# Remote_Board_V2_0.net
KiCad netlist of a schematic drawn in EAGLE
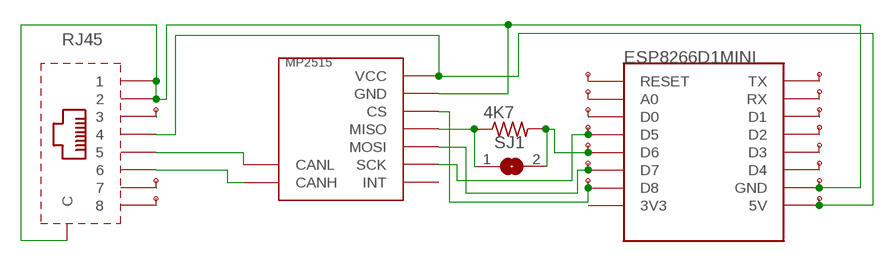
[diagram p0: schematic, sheet 1]

(export (version "E")
  (design (tool "Eeschema 10.0.6"))
  (components
    (comp (ref "4K7")
      (value "R-US_0207/10")
      (footprint "eagle-import:0207_10")
      (libsource (lib "eagle-import") (part "R-US_0207/10"))
    )
    (comp (ref "ESP8266D1MINI")
      (value "WEMOS-D1-MINI_SEM_LAYOUT")
      (footprint "eagle-import:WEMOS-D1-MINI_SEM_LAYOUT")
      (libsource (lib "eagle-import") (part "WEMOS-D1-MINI_SEM_LAYOUT"))
    )
    (comp (ref "RJ45")
      (value "ALI-RJ45_SEM_LAYOUT")
      (footprint "eagle-import:ALI-RJ45_SEM_LAYOUT")
      (libsource (lib "eagle-import") (part "ALI-RJ45_SEM_LAYOUT"))
    )
    (comp (ref "SJ1") (value "SJ") (footprint "eagle-import:SJ") (libsource (lib "eagle-import") (part "SJ")))
    (comp (ref "U$1") (value "TP") (footprint "eagle-import:TP") (libsource (lib "eagle-import") (part "TP")))
    (comp (ref "U$2") (value "TP") (footprint "eagle-import:TP") (libsource (lib "eagle-import") (part "TP")))
    (comp (ref "U$3") (value "TP") (footprint "eagle-import:TP") (libsource (lib "eagle-import") (part "TP")))
    (comp (ref "U$4") (value "TP") (footprint "eagle-import:TP") (libsource (lib "eagle-import") (part "TP")))
    (comp (ref "U$5") (value "TP") (footprint "eagle-import:TP") (libsource (lib "eagle-import") (part "TP")))
    (comp (ref "U$6") (value "TP") (footprint "eagle-import:TP") (libsource (lib "eagle-import") (part "TP")))
    (comp (ref "U$7") (value "TP") (footprint "eagle-import:TP") (libsource (lib "eagle-import") (part "TP")))
    (comp (ref "U$8") (value "TP") (footprint "eagle-import:TP") (libsource (lib "eagle-import") (part "TP")))
    (comp (ref "U$9") (value "TP") (footprint "eagle-import:TP") (libsource (lib "eagle-import") (part "TP")))
    (comp (ref "U$10")
      (value "TP")
      (footprint "eagle-import:TP")
      (libsource (lib "eagle-import") (part "TP"))
    )
    (comp (ref "U$11")
      (value "TP")
      (footprint "eagle-import:TP")
      (libsource (lib "eagle-import") (part "TP"))
    )
    (comp (ref "U$12")
      (value "TP")
      (footprint "eagle-import:TP")
      (libsource (lib "eagle-import") (part "TP"))
    )
    (comp (ref "U$13")
      (value "TP")
      (footprint "eagle-import:TP")
      (libsource (lib "eagle-import") (part "TP"))
    )
    (comp (ref "U$14")
      (value "TP")
      (footprint "eagle-import:TP")
      (libsource (lib "eagle-import") (part "TP"))
    )
    (comp (ref "U$15")
      (value "TP")
      (footprint "eagle-import:TP")
      (libsource (lib "eagle-import") (part "TP"))
    )
    (comp (ref "U$16")
      (value "TP")
      (footprint "eagle-import:TP")
      (libsource (lib "eagle-import") (part "TP"))
    )
    (comp (ref "U$17")
      (value "TP")
      (footprint "eagle-import:TP")
      (libsource (lib "eagle-import") (part "TP"))
    )
    (comp (ref "U$18")
      (value "TP")
      (footprint "eagle-import:TP")
      (libsource (lib "eagle-import") (part "TP"))
    )
    (comp (ref "U$31")
      (value "MCP2515_MODULE_SEM_LAYOUT")
      (footprint "eagle-import:MCP2515_MODULE_SEM_LAYOUT")
      (libsource (lib "eagle-import") (part "MCP2515_MODULE_SEM_LAYOUT"))
    )
  )
  (nets
    (net (code "1") (name "Net-(4K7-Pad1)") (class "Default")
      (node (ref "4K7") (pin "1") (pinfunction "1_1") (pintype "passive"))
      (node (ref "SJ1") (pin "1") (pinfunction "1_1") (pintype "passive"))
      (node (ref "U$31") (pin "MISO") (pinfunction "MISO_MISO") (pintype "bidirectional"))
    )
    (net (code "2") (name "Net-(4K7-Pad2)") (class "Default")
      (node (ref "4K7") (pin "2") (pinfunction "2_2") (pintype "passive"))
      (node (ref "ESP8266D1MINI") (pin "D6") (pinfunction "D6_D6") (pintype "bidirectional"))
      (node (ref "SJ1") (pin "2") (pinfunction "2_2") (pintype "passive"))
      (node (ref "U$5") (pin "P$1") (pinfunction "P$1_P$1") (pintype "bidirectional"))
    )
    (net (code "3") (name "Net-(ESP8266D1MINI-Pad5V)") (class "Default")
      (node (ref "ESP8266D1MINI") (pin "5V") (pinfunction "5V_5V") (pintype "bidirectional"))
      (node (ref "RJ45") (pin "4") (pinfunction "4_4") (pintype "bidirectional"))
      (node (ref "U$16") (pin "P$1") (pinfunction "P$1_P$1") (pintype "bidirectional"))
      (node (ref "U$31") (pin "VCC") (pinfunction "VCC_VCC") (pintype "bidirectional"))
    )
    (net (code "4") (name "Net-(ESP8266D1MINI-PadA0)") (class "Default")
      (node (ref "ESP8266D1MINI") (pin "A0") (pinfunction "A0_A0") (pintype "bidirectional"))
      (node (ref "U$2") (pin "P$1") (pinfunction "P$1_P$1") (pintype "bidirectional"))
    )
    (net (code "5") (name "Net-(ESP8266D1MINI-PadD0)") (class "Default")
      (node (ref "ESP8266D1MINI") (pin "D0") (pinfunction "D0_D0") (pintype "bidirectional"))
      (node (ref "U$3") (pin "P$1") (pinfunction "P$1_P$1") (pintype "bidirectional"))
    )
    (net (code "6") (name "Net-(ESP8266D1MINI-PadD1)") (class "Default")
      (node (ref "ESP8266D1MINI") (pin "D1") (pinfunction "D1_D1") (pintype "bidirectional"))
      (node (ref "U$11") (pin "P$1") (pinfunction "P$1_P$1") (pintype "bidirectional"))
    )
    (net (code "7") (name "Net-(ESP8266D1MINI-PadD2)") (class "Default")
      (node (ref "ESP8266D1MINI") (pin "D2") (pinfunction "D2_D2") (pintype "bidirectional"))
      (node (ref "U$12") (pin "P$1") (pinfunction "P$1_P$1") (pintype "bidirectional"))
    )
    (net (code "8") (name "Net-(ESP8266D1MINI-PadD3)") (class "Default")
      (node (ref "ESP8266D1MINI") (pin "D3") (pinfunction "D3_D3") (pintype "bidirectional"))
      (node (ref "U$13") (pin "P$1") (pinfunction "P$1_P$1") (pintype "bidirectional"))
    )
    (net (code "9") (name "Net-(ESP8266D1MINI-PadD4)") (class "Default")
      (node (ref "ESP8266D1MINI") (pin "D4") (pinfunction "D4_D4") (pintype "bidirectional"))
      (node (ref "U$14") (pin "P$1") (pinfunction "P$1_P$1") (pintype "bidirectional"))
    )
    (net (code "10") (name "Net-(ESP8266D1MINI-PadD5)") (class "Default")
      (node (ref "ESP8266D1MINI") (pin "D5") (pinfunction "D5_D5") (pintype "bidirectional"))
      (node (ref "U$31") (pin "SCK") (pinfunction "SCK_SCK") (pintype "bidirectional"))
      (node (ref "U$4") (pin "P$1") (pinfunction "P$1_P$1") (pintype "bidirectional"))
    )
    (net (code "11") (name "Net-(ESP8266D1MINI-PadD7)") (class "Default")
      (node (ref "ESP8266D1MINI") (pin "D7") (pinfunction "D7_D7") (pintype "bidirectional"))
      (node (ref "U$31") (pin "MOSI") (pinfunction "MOSI_MOSI") (pintype "bidirectional"))
      (node (ref "U$8") (pin "P$1") (pinfunction "P$1_P$1") (pintype "bidirectional"))
    )
    (net (code "12") (name "Net-(ESP8266D1MINI-PadD8)") (class "Default")
      (node (ref "ESP8266D1MINI") (pin "D8") (pinfunction "D8_D8") (pintype "bidirectional"))
      (node (ref "U$31") (pin "CS") (pinfunction "CS_CS") (pintype "bidirectional"))
      (node (ref "U$9") (pin "P$1") (pinfunction "P$1_P$1") (pintype "bidirectional"))
    )
    (net (code "13") (name "Net-(ESP8266D1MINI-PadGND)") (class "Default")
      (node (ref "ESP8266D1MINI") (pin "GND") (pinfunction "GND_GND") (pintype "bidirectional"))
      (node (ref "RJ45") (pin "1") (pinfunction "1_1") (pintype "bidirectional"))
      (node (ref "RJ45") (pin "2") (pinfunction "2_2") (pintype "bidirectional"))
      (node (ref "RJ45") (pin "P$1") (pinfunction "C_P$1") (pintype "bidirectional"))
      (node (ref "RJ45") (pin "P$2") (pinfunction "C_P$2") (pintype "bidirectional"))
      (node (ref "U$15") (pin "P$1") (pinfunction "P$1_P$1") (pintype "bidirectional"))
      (node (ref "U$31") (pin "GND") (pinfunction "GND_GND") (pintype "bidirectional"))
    )
    (net (code "14") (name "Net-(ESP8266D1MINI-PadRESET)") (class "Default")
      (node (ref "ESP8266D1MINI") (pin "RESET") (pinfunction "RESET_RESET") (pintype "bidirectional"))
      (node (ref "U$1") (pin "P$1") (pinfunction "P$1_P$1") (pintype "bidirectional"))
    )
    (net (code "15") (name "Net-(ESP8266D1MINI-PadRX)") (class "Default")
      (node (ref "ESP8266D1MINI") (pin "RX") (pinfunction "RX_RX") (pintype "bidirectional"))
      (node (ref "U$7") (pin "P$1") (pinfunction "P$1_P$1") (pintype "bidirectional"))
    )
    (net (code "16") (name "Net-(ESP8266D1MINI-PadTX)") (class "Default")
      (node (ref "ESP8266D1MINI") (pin "TX") (pinfunction "TX_TX") (pintype "bidirectional"))
      (node (ref "U$6") (pin "P$1") (pinfunction "P$1_P$1") (pintype "bidirectional"))
    )
    (net (code "17") (name "Net-(RJ45-Pad3)") (class "Default")
      (node (ref "RJ45") (pin "3") (pinfunction "3_3") (pintype "bidirectional"))
      (node (ref "U$10") (pin "P$1") (pinfunction "P$1_P$1") (pintype "bidirectional"))
    )
    (net (code "18") (name "Net-(RJ45-Pad7)") (class "Default")
      (node (ref "RJ45") (pin "7") (pinfunction "7_7") (pintype "bidirectional"))
      (node (ref "U$17") (pin "P$1") (pinfunction "P$1_P$1") (pintype "bidirectional"))
    )
    (net (code "19") (name "Net-(RJ45-Pad8)") (class "Default")
      (node (ref "RJ45") (pin "8") (pinfunction "8_8") (pintype "bidirectional"))
      (node (ref "U$18") (pin "P$1") (pinfunction "P$1_P$1") (pintype "bidirectional"))
    )
    (net (code "20") (name "Net-(U$31-CANH)") (class "Default")
      (node (ref "RJ45") (pin "6") (pinfunction "6_6") (pintype "bidirectional"))
      (node (ref "U$31") (pin "CH") (pinfunction "CANH_CH") (pintype "bidirectional"))
    )
    (net (code "21") (name "Net-(U$31-CANL)") (class "Default")
      (node (ref "RJ45") (pin "5") (pinfunction "5_5") (pintype "bidirectional"))
      (node (ref "U$31") (pin "CL") (pinfunction "CANL_CL") (pintype "bidirectional"))
    )
    (net (code "22") (name "unconnected-(ESP8266D1MINI-Pad3V3)") (class "Default")
      (node (ref "ESP8266D1MINI") (pin "3V3") (pinfunction "3V3_3V3") (pintype "bidirectional"))
    )
    (net (code "23") (name "unconnected-(U$31-PadINT)") (class "Default")
      (node (ref "U$31") (pin "INT") (pinfunction "INT_INT") (pintype "bidirectional"))
    )
  )
)
